# ZynqPL.net
KiCad netlist of a schematic drawn in Altium Designer
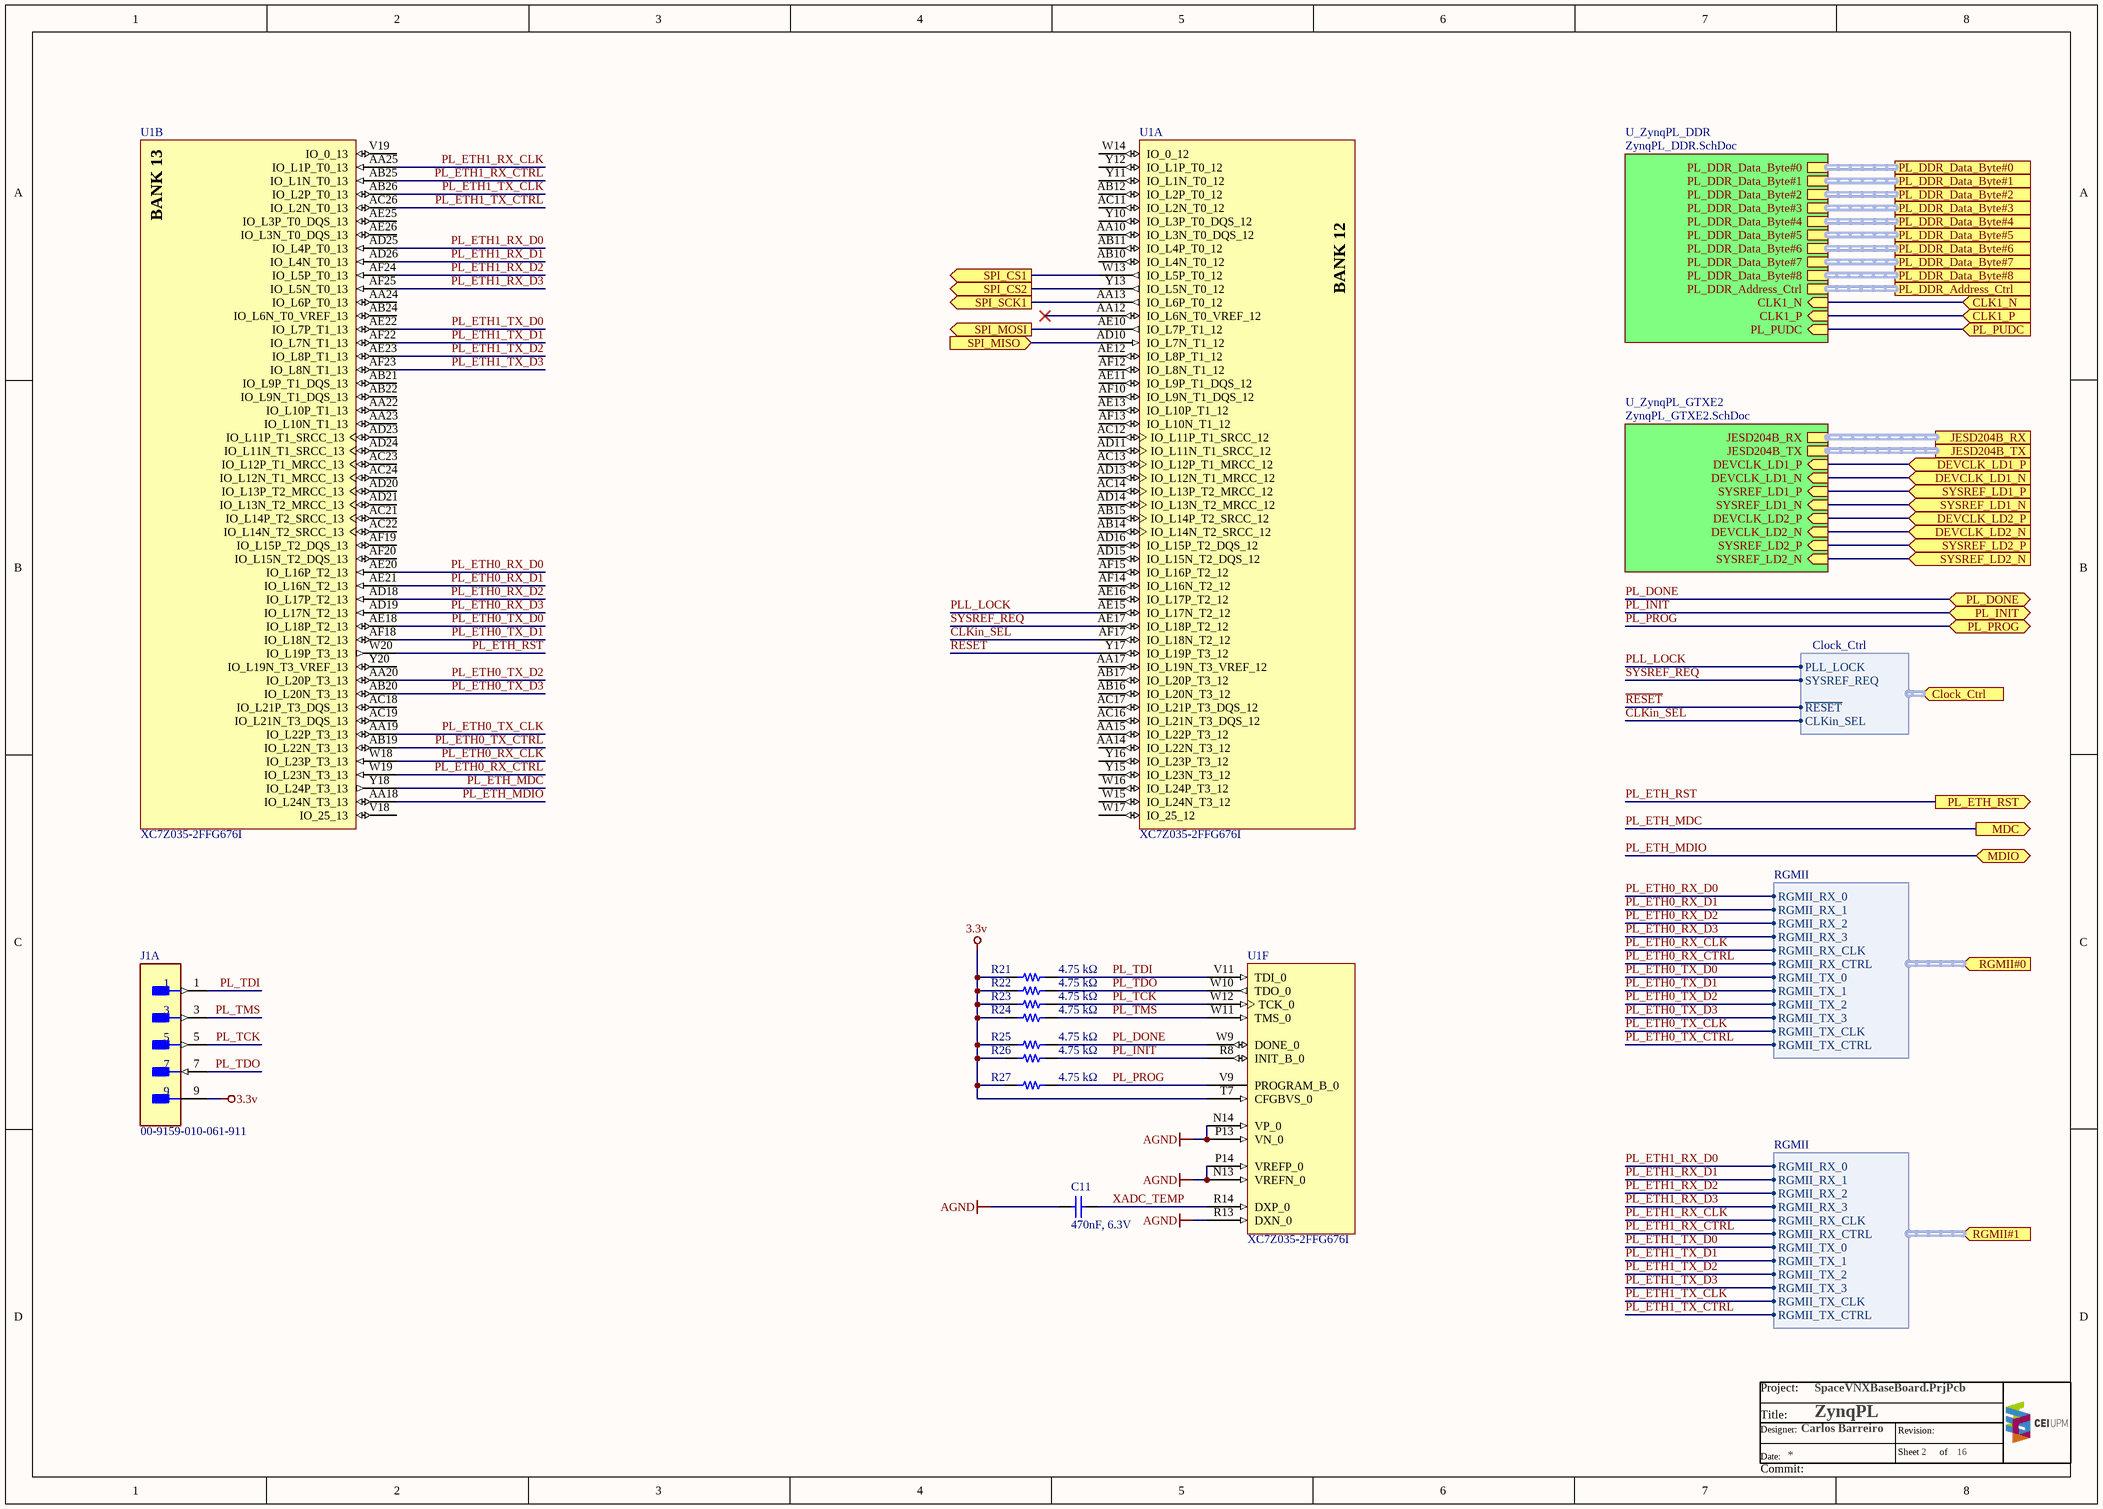
[diagram p0: ZynqPL.SchDoc]

(export (version "E")
  (design (tool "Eeschema 10.0.6"))
  (components
    (comp (ref "C11")
      (value "470nF, 6.3V")
      (footprint "WURTH_WCAP-CSGP_0402")
      (description "WCAP-CSGP Multilayer Ceramic Chip Capacitor, General Purpose, size 0402, X5R, 470nF, 6.3V")
      (fields
        (field (name "MANUFACTURER PART NUMBER") "885012105004")
        (field (name "MANUFACTURER") "Wurth Elektronik")
      )
      (libsource (lib "SpaceVNX") (part "885012105004"))
    )
    (comp (ref "J1")
      (value "00-9159-010-061-911")
      (footprint "KYOCERA_00-9159-010-061-911")
      (description "Coplanar Open Ended Card Edge Connector 10 Pin")
      (libsource (lib "SpaceVNX") (part "00-9159-010-061-911"))
    )
    (comp (ref "R21")
      (value "4.75 kΩ")
      (footprint "PANASONIC_ERJ2G_0402")
      (description "General Purpose Thick Film Chip Resistors")
      (fields (field (name "MANUFACTURER") "Panasonic"))
      (libsource (lib "SpaceVNX") (part "ERJ2RKF4751X"))
    )
    (comp (ref "R22")
      (value "4.75 kΩ")
      (footprint "PANASONIC_ERJ2G_0402")
      (description "General Purpose Thick Film Chip Resistors")
      (fields (field (name "MANUFACTURER") "Panasonic"))
      (libsource (lib "SpaceVNX") (part "ERJ2RKF4751X"))
    )
    (comp (ref "R23")
      (value "4.75 kΩ")
      (footprint "PANASONIC_ERJ2G_0402")
      (description "General Purpose Thick Film Chip Resistors")
      (fields (field (name "MANUFACTURER") "Panasonic"))
      (libsource (lib "SpaceVNX") (part "ERJ2RKF4751X"))
    )
    (comp (ref "R24")
      (value "4.75 kΩ")
      (footprint "PANASONIC_ERJ2G_0402")
      (description "General Purpose Thick Film Chip Resistors")
      (fields (field (name "MANUFACTURER") "Panasonic"))
      (libsource (lib "SpaceVNX") (part "ERJ2RKF4751X"))
    )
    (comp (ref "R25")
      (value "4.75 kΩ")
      (footprint "PANASONIC_ERJ2G_0402")
      (description "General Purpose Thick Film Chip Resistors")
      (fields (field (name "MANUFACTURER") "Panasonic"))
      (libsource (lib "SpaceVNX") (part "ERJ2RKF4751X"))
    )
    (comp (ref "R26")
      (value "4.75 kΩ")
      (footprint "PANASONIC_ERJ2G_0402")
      (description "General Purpose Thick Film Chip Resistors")
      (fields (field (name "MANUFACTURER") "Panasonic"))
      (libsource (lib "SpaceVNX") (part "ERJ2RKF4751X"))
    )
    (comp (ref "R27")
      (value "4.75 kΩ")
      (footprint "PANASONIC_ERJ2G_0402")
      (description "General Purpose Thick Film Chip Resistors")
      (fields (field (name "MANUFACTURER") "Panasonic"))
      (libsource (lib "SpaceVNX") (part "ERJ2RKF4751X"))
    )
    (comp (ref "U1")
      (value "XC7Z035-2FFG676I")
      (footprint "XILINX_FBG676")
      (fields (field (name "PARTNUMBER") "XC7Z035-2FBG676I") (field (name "GENERIC PART NUMBER") "XC7Z035"))
      (libsource (lib "") (part "XC7Z035-2FFG676I_1"))
    )
  )
  (nets
    (net (code "17") (name "/CLKin_SEL") (class "Default")
      (node (ref "U1") (pin "AF17") (pinfunction "IO_L18N_T2_12_AF17") (pintype "bidirectional"))
    )
    (net (code "24") (name "/PLL_LOCK") (class "Default")
      (node (ref "U1") (pin "AE15") (pinfunction "IO_L17N_T2_12_AE15") (pintype "bidirectional"))
    )
    (net (code "35") (name "/PL_DONE") (class "Default")
      (node (ref "R25") (pin "2") (pinfunction "2_2") (pintype "passive"))
      (node (ref "U1") (pin "W9") (pinfunction "DONE_0_W9") (pintype "bidirectional"))
    )
    (net (code "36") (name "/PL_ETH0_RX_CLK") (class "Default")
      (node (ref "U1") (pin "W18") (pinfunction "IO_L23P_T3_13_W18") (pintype "input"))
    )
    (net (code "37") (name "/PL_ETH0_RX_CTRL") (class "Default")
      (node (ref "U1") (pin "W19") (pinfunction "IO_L23N_T3_13_W19") (pintype "input"))
    )
    (net (code "38") (name "/PL_ETH0_RX_D0") (class "Default")
      (node (ref "U1") (pin "AE20") (pinfunction "IO_L16P_T2_13_AE20") (pintype "input"))
    )
    (net (code "39") (name "/PL_ETH0_RX_D1") (class "Default")
      (node (ref "U1") (pin "AE21") (pinfunction "IO_L16N_T2_13_AE21") (pintype "input"))
    )
    (net (code "40") (name "/PL_ETH0_RX_D2") (class "Default")
      (node (ref "U1") (pin "AD18") (pinfunction "IO_L17P_T2_13_AD18") (pintype "input"))
    )
    (net (code "41") (name "/PL_ETH0_RX_D3") (class "Default")
      (node (ref "U1") (pin "AD19") (pinfunction "IO_L17N_T2_13_AD19") (pintype "input"))
    )
    (net (code "42") (name "/PL_ETH0_TX_CLK") (class "Default")
      (node (ref "U1") (pin "AA19") (pinfunction "IO_L22P_T3_13_AA19") (pintype "bidirectional"))
    )
    (net (code "43") (name "/PL_ETH0_TX_CTRL") (class "Default")
      (node (ref "U1") (pin "AB19") (pinfunction "IO_L22N_T3_13_AB19") (pintype "bidirectional"))
    )
    (net (code "44") (name "/PL_ETH0_TX_D0") (class "Default")
      (node (ref "U1") (pin "AE18") (pinfunction "IO_L18P_T2_13_AE18") (pintype "bidirectional"))
    )
    (net (code "45") (name "/PL_ETH0_TX_D1") (class "Default")
      (node (ref "U1") (pin "AF18") (pinfunction "IO_L18N_T2_13_AF18") (pintype "bidirectional"))
    )
    (net (code "46") (name "/PL_ETH0_TX_D2") (class "Default")
      (node (ref "U1") (pin "AA20") (pinfunction "IO_L20P_T3_13_AA20") (pintype "bidirectional"))
    )
    (net (code "47") (name "/PL_ETH0_TX_D3") (class "Default")
      (node (ref "U1") (pin "AB20") (pinfunction "IO_L20N_T3_13_AB20") (pintype "bidirectional"))
    )
    (net (code "48") (name "/PL_ETH1_RX_CLK") (class "Default")
      (node (ref "U1") (pin "AA25") (pinfunction "IO_L1P_T0_13_AA25") (pintype "input"))
    )
    (net (code "49") (name "/PL_ETH1_RX_CTRL") (class "Default")
      (node (ref "U1") (pin "AB25") (pinfunction "IO_L1N_T0_13_AB25") (pintype "input"))
    )
    (net (code "50") (name "/PL_ETH1_RX_D0") (class "Default")
      (node (ref "U1") (pin "AD25") (pinfunction "IO_L4P_T0_13_AD25") (pintype "input"))
    )
    (net (code "51") (name "/PL_ETH1_RX_D1") (class "Default")
      (node (ref "U1") (pin "AD26") (pinfunction "IO_L4N_T0_13_AD26") (pintype "input"))
    )
    (net (code "52") (name "/PL_ETH1_RX_D2") (class "Default")
      (node (ref "U1") (pin "AF24") (pinfunction "IO_L5P_T0_13_AF24") (pintype "input"))
    )
    (net (code "53") (name "/PL_ETH1_RX_D3") (class "Default")
      (node (ref "U1") (pin "AF25") (pinfunction "IO_L5N_T0_13_AF25") (pintype "input"))
    )
    (net (code "54") (name "/PL_ETH1_TX_CLK") (class "Default")
      (node (ref "U1") (pin "AB26") (pinfunction "IO_L2P_T0_13_AB26") (pintype "bidirectional"))
    )
    (net (code "55") (name "/PL_ETH1_TX_CTRL") (class "Default")
      (node (ref "U1") (pin "AC26") (pinfunction "IO_L2N_T0_13_AC26") (pintype "bidirectional"))
    )
    (net (code "56") (name "/PL_ETH1_TX_D0") (class "Default")
      (node (ref "U1") (pin "AE22") (pinfunction "IO_L7P_T1_13_AE22") (pintype "bidirectional"))
    )
    (net (code "57") (name "/PL_ETH1_TX_D1") (class "Default")
      (node (ref "U1") (pin "AF22") (pinfunction "IO_L7N_T1_13_AF22") (pintype "bidirectional"))
    )
    (net (code "58") (name "/PL_ETH1_TX_D2") (class "Default")
      (node (ref "U1") (pin "AE23") (pinfunction "IO_L8P_T1_13_AE23") (pintype "bidirectional"))
    )
    (net (code "59") (name "/PL_ETH1_TX_D3") (class "Default")
      (node (ref "U1") (pin "AF23") (pinfunction "IO_L8N_T1_13_AF23") (pintype "bidirectional"))
    )
    (net (code "60") (name "/PL_ETH_MDC") (class "Default")
      (node (ref "U1") (pin "Y18") (pinfunction "IO_L24P_T3_13_Y18") (pintype "output"))
    )
    (net (code "61") (name "/PL_ETH_MDIO") (class "Default")
      (node (ref "U1") (pin "AA18") (pinfunction "IO_L24N_T3_13_AA18") (pintype "bidirectional"))
    )
    (net (code "62") (name "/PL_ETH_RST") (class "Default")
      (node (ref "U1") (pin "W20") (pinfunction "IO_L19P_T3_13_W20") (pintype "output"))
    )
    (net (code "63") (name "/PL_INIT") (class "Default")
      (node (ref "R26") (pin "2") (pinfunction "2_2") (pintype "passive"))
      (node (ref "U1") (pin "R8") (pinfunction "INIT_B_0_R8") (pintype "bidirectional"))
    )
    (net (code "64") (name "/PL_PROG") (class "Default")
      (node (ref "R27") (pin "2") (pinfunction "2_2") (pintype "passive"))
      (node (ref "U1") (pin "V9") (pinfunction "PROGRAM_B_0_V9") (pintype "input"))
    )
    (net (code "66") (name "/PL_TCK") (class "Default")
      (node (ref "J1") (pin "5") (pinfunction "5_5") (pintype "output"))
      (node (ref "R23") (pin "2") (pinfunction "2_2") (pintype "passive"))
      (node (ref "U1") (pin "W12") (pinfunction "TCK_0_W12") (pintype "input"))
    )
    (net (code "67") (name "/PL_TDI") (class "Default")
      (node (ref "J1") (pin "1") (pinfunction "1_1") (pintype "output"))
      (node (ref "R21") (pin "2") (pinfunction "2_2") (pintype "passive"))
      (node (ref "U1") (pin "V11") (pinfunction "TDI_0_V11") (pintype "input"))
    )
    (net (code "68") (name "/PL_TDO") (class "Default")
      (node (ref "J1") (pin "7") (pinfunction "7_7") (pintype "input"))
      (node (ref "R22") (pin "2") (pinfunction "2_2") (pintype "passive"))
      (node (ref "U1") (pin "W10") (pinfunction "TDO_0_W10") (pintype "output"))
    )
    (net (code "69") (name "/PL_TMS") (class "Default")
      (node (ref "J1") (pin "3") (pinfunction "3_3") (pintype "output"))
      (node (ref "R24") (pin "2") (pinfunction "2_2") (pintype "passive"))
      (node (ref "U1") (pin "W11") (pinfunction "TMS_0_W11") (pintype "input"))
    )
    (net (code "70") (name "/SPI_CS1") (class "Default")
      (node (ref "U1") (pin "W13") (pinfunction "IO_L5P_T0_12_W13") (pintype "output"))
    )
    (net (code "71") (name "/SPI_CS2") (class "Default")
      (node (ref "U1") (pin "Y13") (pinfunction "IO_L5N_T0_12_Y13") (pintype "output"))
    )
    (net (code "72") (name "/SPI_MISO") (class "Default")
      (node (ref "U1") (pin "AD10") (pinfunction "IO_L7N_T1_12_AD10") (pintype "input"))
    )
    (net (code "73") (name "/SPI_MOSI") (class "Default")
      (node (ref "U1") (pin "AE10") (pinfunction "IO_L7P_T1_12_AE10") (pintype "output"))
    )
    (net (code "74") (name "/SPI_SCK1") (class "Default")
      (node (ref "U1") (pin "AA13") (pinfunction "IO_L6P_T0_12_AA13") (pintype "output"))
    )
    (net (code "79") (name "/SYSREF_REQ") (class "Default")
      (node (ref "U1") (pin "AE17") (pinfunction "IO_L18P_T2_12_AE17") (pintype "bidirectional"))
    )
    (net (code "80") (name "/XADC_TEMP") (class "Default")
      (node (ref "C11") (pin "2") (pinfunction "2_2") (pintype "passive"))
      (node (ref "U1") (pin "R14") (pinfunction "DXP_0_R14") (pintype "input"))
    )
    (net (code "83") (name "/~{RESET}") (class "Default")
      (node (ref "U1") (pin "Y17") (pinfunction "IO_L19P_T3_12_Y17") (pintype "bidirectional"))
    )
    (net (code "84") (name "3.3v") (class "Default")
      (node (ref "J1") (pin "9") (pinfunction "9_9") (pintype "power_in"))
      (node (ref "R21") (pin "1") (pinfunction "1_1") (pintype "passive"))
      (node (ref "R22") (pin "1") (pinfunction "1_1") (pintype "passive"))
      (node (ref "R23") (pin "1") (pinfunction "1_1") (pintype "passive"))
      (node (ref "R24") (pin "1") (pinfunction "1_1") (pintype "passive"))
      (node (ref "R25") (pin "1") (pinfunction "1_1") (pintype "passive"))
      (node (ref "R26") (pin "1") (pinfunction "1_1") (pintype "passive"))
      (node (ref "R27") (pin "1") (pinfunction "1_1") (pintype "passive"))
      (node (ref "U1") (pin "T7") (pinfunction "CFGBVS_0_T7") (pintype "input"))
    )
    (net (code "85") (name "AGND") (class "Default")
      (node (ref "C11") (pin "1") (pinfunction "1_1") (pintype "passive"))
      (node (ref "U1") (pin "N13") (pinfunction "VREFN_0_N13") (pintype "input"))
      (node (ref "U1") (pin "N14") (pinfunction "VP_0_N14") (pintype "input"))
      (node (ref "U1") (pin "P13") (pinfunction "VN_0_P13") (pintype "input"))
      (node (ref "U1") (pin "P14") (pinfunction "VREFP_0_P14") (pintype "input"))
      (node (ref "U1") (pin "R13") (pinfunction "DXN_0_R13") (pintype "input"))
    )
    (net (code "86") (name "unconnected-(U1A-IO_0_12-PadW14)") (class "Default")
      (node (ref "U1") (pin "W14") (pinfunction "IO_0_12_W14") (pintype "bidirectional"))
    )
    (net (code "87") (name "unconnected-(U1A-IO_25_12-PadW17)") (class "Default")
      (node (ref "U1") (pin "W17") (pinfunction "IO_25_12_W17") (pintype "bidirectional"))
    )
    (net (code "88") (name "unconnected-(U1A-IO_L1N_T0_12-PadY11)") (class "Default")
      (node (ref "U1") (pin "Y11") (pinfunction "IO_L1N_T0_12_Y11") (pintype "bidirectional"))
    )
    (net (code "89") (name "unconnected-(U1A-IO_L1P_T0_12-PadY12)") (class "Default")
      (node (ref "U1") (pin "Y12") (pinfunction "IO_L1P_T0_12_Y12") (pintype "bidirectional"))
    )
    (net (code "90") (name "unconnected-(U1A-IO_L2N_T0_12-PadAC11)") (class "Default")
      (node (ref "U1") (pin "AC11") (pinfunction "IO_L2N_T0_12_AC11") (pintype "bidirectional"))
    )
    (net (code "91") (name "unconnected-(U1A-IO_L2P_T0_12-PadAB12)") (class "Default")
      (node (ref "U1") (pin "AB12") (pinfunction "IO_L2P_T0_12_AB12") (pintype "bidirectional"))
    )
    (net (code "92") (name "unconnected-(U1A-IO_L3N_T0_DQS_12-PadAA10)") (class "Default")
      (node (ref "U1") (pin "AA10") (pinfunction "IO_L3N_T0_DQS_12_AA10") (pintype "bidirectional"))
    )
    (net (code "93") (name "unconnected-(U1A-IO_L3P_T0_DQS_12-PadY10)") (class "Default")
      (node (ref "U1") (pin "Y10") (pinfunction "IO_L3P_T0_DQS_12_Y10") (pintype "bidirectional"))
    )
    (net (code "94") (name "unconnected-(U1A-IO_L4N_T0_12-PadAB10)") (class "Default")
      (node (ref "U1") (pin "AB10") (pinfunction "IO_L4N_T0_12_AB10") (pintype "bidirectional"))
    )
    (net (code "95") (name "unconnected-(U1A-IO_L4P_T0_12-PadAB11)") (class "Default")
      (node (ref "U1") (pin "AB11") (pinfunction "IO_L4P_T0_12_AB11") (pintype "bidirectional"))
    )
    (net (code "96") (name "unconnected-(U1A-IO_L6N_T0_VREF_12-PadAA12)") (class "Default")
      (node (ref "U1") (pin "AA12") (pinfunction "IO_L6N_T0_VREF_12_AA12") (pintype "bidirectional+no_connect"))
    )
    (net (code "97") (name "unconnected-(U1A-IO_L8N_T1_12-PadAF12)") (class "Default")
      (node (ref "U1") (pin "AF12") (pinfunction "IO_L8N_T1_12_AF12") (pintype "bidirectional"))
    )
    (net (code "98") (name "unconnected-(U1A-IO_L8P_T1_12-PadAE12)") (class "Default")
      (node (ref "U1") (pin "AE12") (pinfunction "IO_L8P_T1_12_AE12") (pintype "bidirectional"))
    )
    (net (code "99") (name "unconnected-(U1A-IO_L9N_T1_DQS_12-PadAF10)") (class "Default")
      (node (ref "U1") (pin "AF10") (pinfunction "IO_L9N_T1_DQS_12_AF10") (pintype "bidirectional"))
    )
    (net (code "100") (name "unconnected-(U1A-IO_L9P_T1_DQS_12-PadAE11)") (class "Default")
      (node (ref "U1") (pin "AE11") (pinfunction "IO_L9P_T1_DQS_12_AE11") (pintype "bidirectional"))
    )
    (net (code "101") (name "unconnected-(U1A-IO_L10N_T1_12-PadAF13)") (class "Default")
      (node (ref "U1") (pin "AF13") (pinfunction "IO_L10N_T1_12_AF13") (pintype "bidirectional"))
    )
    (net (code "102") (name "unconnected-(U1A-IO_L10P_T1_12-PadAE13)") (class "Default")
      (node (ref "U1") (pin "AE13") (pinfunction "IO_L10P_T1_12_AE13") (pintype "bidirectional"))
    )
    (net (code "103") (name "unconnected-(U1A-IO_L11N_T1_SRCC_12-PadAD11)") (class "Default")
      (node (ref "U1") (pin "AD11") (pinfunction "IO_L11N_T1_SRCC_12_AD11") (pintype "bidirectional"))
    )
    (net (code "104") (name "unconnected-(U1A-IO_L11P_T1_SRCC_12-PadAC12)") (class "Default")
      (node (ref "U1") (pin "AC12") (pinfunction "IO_L11P_T1_SRCC_12_AC12") (pintype "bidirectional"))
    )
    (net (code "105") (name "unconnected-(U1A-IO_L12N_T1_MRCC_12-PadAD13)") (class "Default")
      (node (ref "U1") (pin "AD13") (pinfunction "IO_L12N_T1_MRCC_12_AD13") (pintype "bidirectional"))
    )
    (net (code "106") (name "unconnected-(U1A-IO_L12P_T1_MRCC_12-PadAC13)") (class "Default")
      (node (ref "U1") (pin "AC13") (pinfunction "IO_L12P_T1_MRCC_12_AC13") (pintype "bidirectional"))
    )
    (net (code "107") (name "unconnected-(U1A-IO_L13N_T2_MRCC_12-PadAD14)") (class "Default")
      (node (ref "U1") (pin "AD14") (pinfunction "IO_L13N_T2_MRCC_12_AD14") (pintype "bidirectional"))
    )
    (net (code "108") (name "unconnected-(U1A-IO_L13P_T2_MRCC_12-PadAC14)") (class "Default")
      (node (ref "U1") (pin "AC14") (pinfunction "IO_L13P_T2_MRCC_12_AC14") (pintype "bidirectional"))
    )
    (net (code "109") (name "unconnected-(U1A-IO_L14N_T2_SRCC_12-PadAB14)") (class "Default")
      (node (ref "U1") (pin "AB14") (pinfunction "IO_L14N_T2_SRCC_12_AB14") (pintype "bidirectional"))
    )
    (net (code "110") (name "unconnected-(U1A-IO_L14P_T2_SRCC_12-PadAB15)") (class "Default")
      (node (ref "U1") (pin "AB15") (pinfunction "IO_L14P_T2_SRCC_12_AB15") (pintype "bidirectional"))
    )
    (net (code "111") (name "unconnected-(U1A-IO_L15N_T2_DQS_12-PadAD15)") (class "Default")
      (node (ref "U1") (pin "AD15") (pinfunction "IO_L15N_T2_DQS_12_AD15") (pintype "bidirectional"))
    )
    (net (code "112") (name "unconnected-(U1A-IO_L15P_T2_DQS_12-PadAD16)") (class "Default")
      (node (ref "U1") (pin "AD16") (pinfunction "IO_L15P_T2_DQS_12_AD16") (pintype "bidirectional"))
    )
    (net (code "113") (name "unconnected-(U1A-IO_L16N_T2_12-PadAF14)") (class "Default")
      (node (ref "U1") (pin "AF14") (pinfunction "IO_L16N_T2_12_AF14") (pintype "bidirectional"))
    )
    (net (code "114") (name "unconnected-(U1A-IO_L16P_T2_12-PadAF15)") (class "Default")
      (node (ref "U1") (pin "AF15") (pinfunction "IO_L16P_T2_12_AF15") (pintype "bidirectional"))
    )
    (net (code "115") (name "unconnected-(U1A-IO_L17P_T2_12-PadAE16)") (class "Default")
      (node (ref "U1") (pin "AE16") (pinfunction "IO_L17P_T2_12_AE16") (pintype "bidirectional"))
    )
    (net (code "116") (name "unconnected-(U1A-IO_L19N_T3_VREF_12-PadAA17)") (class "Default")
      (node (ref "U1") (pin "AA17") (pinfunction "IO_L19N_T3_VREF_12_AA17") (pintype "bidirectional"))
    )
    (net (code "117") (name "unconnected-(U1A-IO_L20N_T3_12-PadAB16)") (class "Default")
      (node (ref "U1") (pin "AB16") (pinfunction "IO_L20N_T3_12_AB16") (pintype "bidirectional"))
    )
    (net (code "118") (name "unconnected-(U1A-IO_L20P_T3_12-PadAB17)") (class "Default")
      (node (ref "U1") (pin "AB17") (pinfunction "IO_L20P_T3_12_AB17") (pintype "bidirectional"))
    )
    (net (code "119") (name "unconnected-(U1A-IO_L21N_T3_DQS_12-PadAC16)") (class "Default")
      (node (ref "U1") (pin "AC16") (pinfunction "IO_L21N_T3_DQS_12_AC16") (pintype "bidirectional"))
    )
    (net (code "120") (name "unconnected-(U1A-IO_L21P_T3_DQS_12-PadAC17)") (class "Default")
      (node (ref "U1") (pin "AC17") (pinfunction "IO_L21P_T3_DQS_12_AC17") (pintype "bidirectional"))
    )
    (net (code "121") (name "unconnected-(U1A-IO_L22N_T3_12-PadAA14)") (class "Default")
      (node (ref "U1") (pin "AA14") (pinfunction "IO_L22N_T3_12_AA14") (pintype "bidirectional"))
    )
    (net (code "122") (name "unconnected-(U1A-IO_L22P_T3_12-PadAA15)") (class "Default")
      (node (ref "U1") (pin "AA15") (pinfunction "IO_L22P_T3_12_AA15") (pintype "bidirectional"))
    )
    (net (code "123") (name "unconnected-(U1A-IO_L23N_T3_12-PadY15)") (class "Default")
      (node (ref "U1") (pin "Y15") (pinfunction "IO_L23N_T3_12_Y15") (pintype "bidirectional"))
    )
    (net (code "124") (name "unconnected-(U1A-IO_L23P_T3_12-PadY16)") (class "Default")
      (node (ref "U1") (pin "Y16") (pinfunction "IO_L23P_T3_12_Y16") (pintype "bidirectional"))
    )
    (net (code "125") (name "unconnected-(U1A-IO_L24N_T3_12-PadW15)") (class "Default")
      (node (ref "U1") (pin "W15") (pinfunction "IO_L24N_T3_12_W15") (pintype "bidirectional"))
    )
    (net (code "126") (name "unconnected-(U1A-IO_L24P_T3_12-PadW16)") (class "Default")
      (node (ref "U1") (pin "W16") (pinfunction "IO_L24P_T3_12_W16") (pintype "bidirectional"))
    )
    (net (code "127") (name "unconnected-(U1B-IO_0_13-PadV19)") (class "Default")
      (node (ref "U1") (pin "V19") (pinfunction "IO_0_13_V19") (pintype "bidirectional"))
    )
    (net (code "128") (name "unconnected-(U1B-IO_25_13-PadV18)") (class "Default")
      (node (ref "U1") (pin "V18") (pinfunction "IO_25_13_V18") (pintype "bidirectional"))
    )
    (net (code "129") (name "unconnected-(U1B-IO_L3N_T0_DQS_13-PadAE26)") (class "Default")
      (node (ref "U1") (pin "AE26") (pinfunction "IO_L3N_T0_DQS_13_AE26") (pintype "bidirectional"))
    )
    (net (code "130") (name "unconnected-(U1B-IO_L3P_T0_DQS_13-PadAE25)") (class "Default")
      (node (ref "U1") (pin "AE25") (pinfunction "IO_L3P_T0_DQS_13_AE25") (pintype "bidirectional"))
    )
    (net (code "131") (name "unconnected-(U1B-IO_L6N_T0_VREF_13-PadAB24)") (class "Default")
      (node (ref "U1") (pin "AB24") (pinfunction "IO_L6N_T0_VREF_13_AB24") (pintype "bidirectional"))
    )
    (net (code "132") (name "unconnected-(U1B-IO_L6P_T0_13-PadAA24)") (class "Default")
      (node (ref "U1") (pin "AA24") (pinfunction "IO_L6P_T0_13_AA24") (pintype "bidirectional"))
    )
    (net (code "133") (name "unconnected-(U1B-IO_L9N_T1_DQS_13-PadAB22)") (class "Default")
      (node (ref "U1") (pin "AB22") (pinfunction "IO_L9N_T1_DQS_13_AB22") (pintype "bidirectional"))
    )
    (net (code "134") (name "unconnected-(U1B-IO_L9P_T1_DQS_13-PadAB21)") (class "Default")
      (node (ref "U1") (pin "AB21") (pinfunction "IO_L9P_T1_DQS_13_AB21") (pintype "bidirectional"))
    )
    (net (code "135") (name "unconnected-(U1B-IO_L10N_T1_13-PadAA23)") (class "Default")
      (node (ref "U1") (pin "AA23") (pinfunction "IO_L10N_T1_13_AA23") (pintype "bidirectional"))
    )
    (net (code "136") (name "unconnected-(U1B-IO_L10P_T1_13-PadAA22)") (class "Default")
      (node (ref "U1") (pin "AA22") (pinfunction "IO_L10P_T1_13_AA22") (pintype "bidirectional"))
    )
    (net (code "137") (name "unconnected-(U1B-IO_L11N_T1_SRCC_13-PadAD24)") (class "Default")
      (node (ref "U1") (pin "AD24") (pinfunction "IO_L11N_T1_SRCC_13_AD24") (pintype "bidirectional"))
    )
    (net (code "138") (name "unconnected-(U1B-IO_L11P_T1_SRCC_13-PadAD23)") (class "Default")
      (node (ref "U1") (pin "AD23") (pinfunction "IO_L11P_T1_SRCC_13_AD23") (pintype "bidirectional"))
    )
    (net (code "139") (name "unconnected-(U1B-IO_L12N_T1_MRCC_13-PadAC24)") (class "Default")
      (node (ref "U1") (pin "AC24") (pinfunction "IO_L12N_T1_MRCC_13_AC24") (pintype "bidirectional"))
    )
    (net (code "140") (name "unconnected-(U1B-IO_L12P_T1_MRCC_13-PadAC23)") (class "Default")
      (node (ref "U1") (pin "AC23") (pinfunction "IO_L12P_T1_MRCC_13_AC23") (pintype "bidirectional"))
    )
    (net (code "141") (name "unconnected-(U1B-IO_L13N_T2_MRCC_13-PadAD21)") (class "Default")
      (node (ref "U1") (pin "AD21") (pinfunction "IO_L13N_T2_MRCC_13_AD21") (pintype "bidirectional"))
    )
    (net (code "142") (name "unconnected-(U1B-IO_L13P_T2_MRCC_13-PadAD20)") (class "Default")
      (node (ref "U1") (pin "AD20") (pinfunction "IO_L13P_T2_MRCC_13_AD20") (pintype "bidirectional"))
    )
    (net (code "143") (name "unconnected-(U1B-IO_L14N_T2_SRCC_13-PadAC22)") (class "Default")
      (node (ref "U1") (pin "AC22") (pinfunction "IO_L14N_T2_SRCC_13_AC22") (pintype "bidirectional"))
    )
    (net (code "144") (name "unconnected-(U1B-IO_L14P_T2_SRCC_13-PadAC21)") (class "Default")
      (node (ref "U1") (pin "AC21") (pinfunction "IO_L14P_T2_SRCC_13_AC21") (pintype "bidirectional"))
    )
    (net (code "145") (name "unconnected-(U1B-IO_L15N_T2_DQS_13-PadAF20)") (class "Default")
      (node (ref "U1") (pin "AF20") (pinfunction "IO_L15N_T2_DQS_13_AF20") (pintype "bidirectional"))
    )
    (net (code "146") (name "unconnected-(U1B-IO_L15P_T2_DQS_13-PadAF19)") (class "Default")
      (node (ref "U1") (pin "AF19") (pinfunction "IO_L15P_T2_DQS_13_AF19") (pintype "bidirectional"))
    )
    (net (code "147") (name "unconnected-(U1B-IO_L19N_T3_VREF_13-PadY20)") (class "Default")
      (node (ref "U1") (pin "Y20") (pinfunction "IO_L19N_T3_VREF_13_Y20") (pintype "bidirectional"))
    )
    (net (code "148") (name "unconnected-(U1B-IO_L21N_T3_DQS_13-PadAC19)") (class "Default")
      (node (ref "U1") (pin "AC19") (pinfunction "IO_L21N_T3_DQS_13_AC19") (pintype "bidirectional"))
    )
    (net (code "149") (name "unconnected-(U1B-IO_L21P_T3_DQS_13-PadAC18)") (class "Default")
      (node (ref "U1") (pin "AC18") (pinfunction "IO_L21P_T3_DQS_13_AC18") (pintype "bidirectional"))
    )
  )
)
